# lightmeter_external_batt_circuit.net
KiCad netlist of a schematic drawn in EAGLE
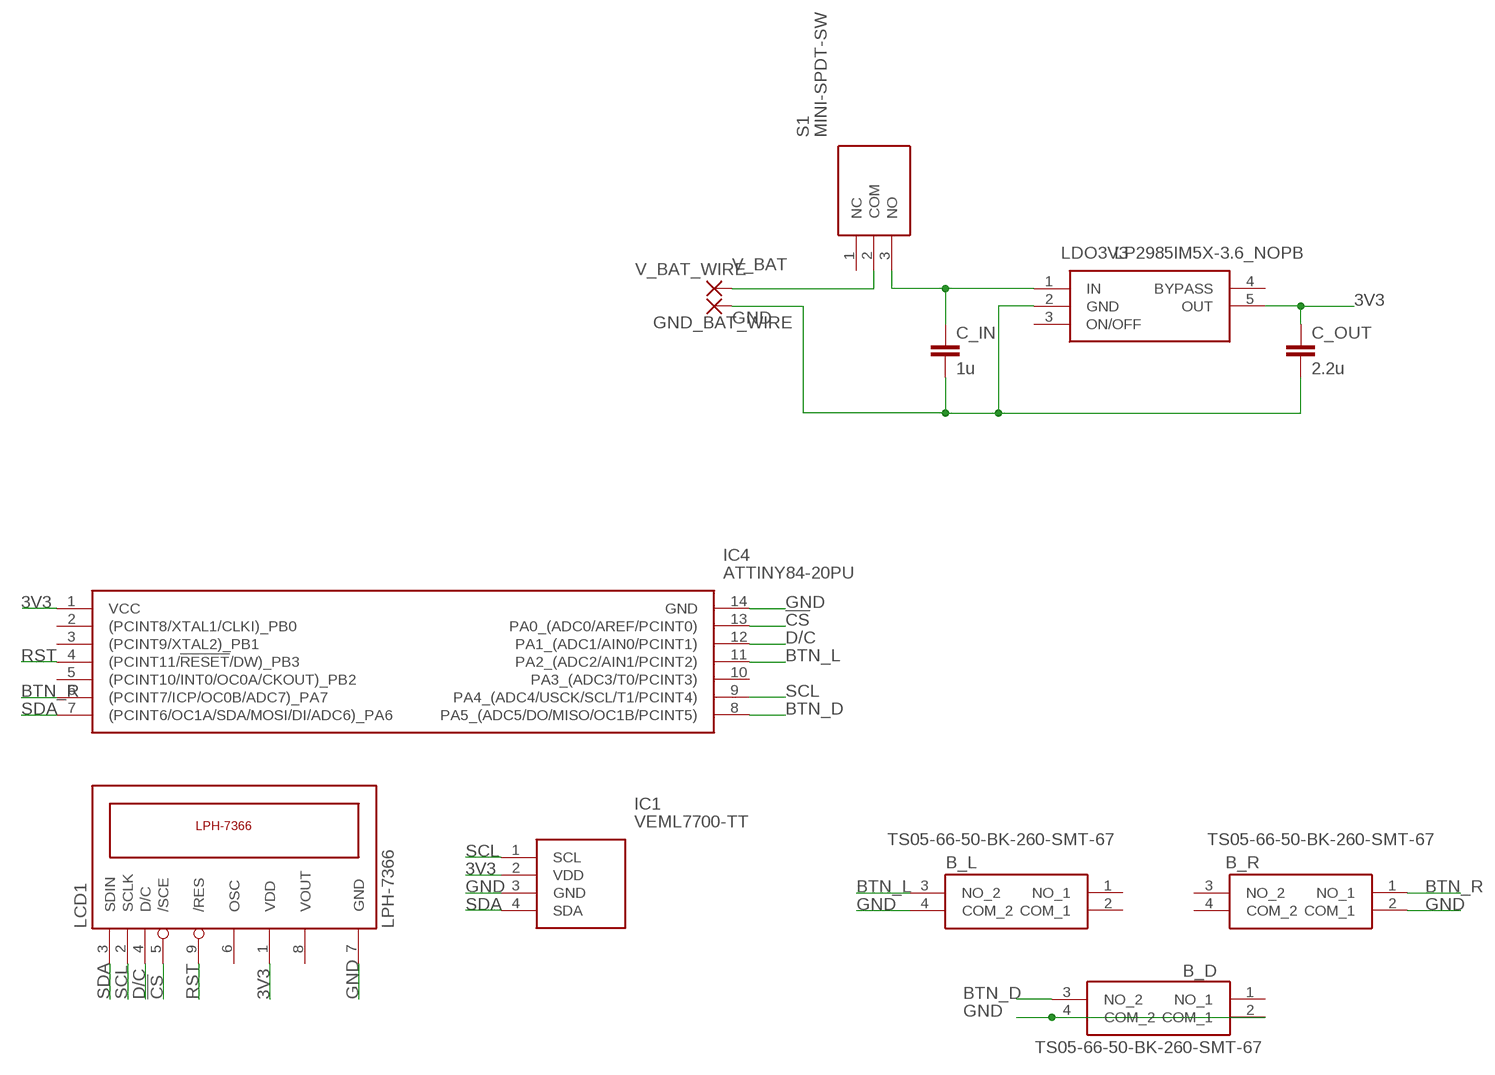
[diagram p0: schematic, sheet 1]

(export (version "E")
  (design (tool "Eeschema 10.0.6"))
  (components
    (comp (ref "B_D")
      (value "TS05-66-50-BK-260-SMT-67")
      (footprint "eagle-import:TS056650BK260SMT67")
      (fields (field (name "MOUSER_PART_NUMBER") "179-TS056650260SMT67"))
      (libsource (lib "eagle-import") (part "TS05-66-50-BK-260-SMT-67"))
    )
    (comp (ref "B_L")
      (value "TS05-66-50-BK-260-SMT-67")
      (footprint "eagle-import:TS056650BK260SMT67")
      (fields (field (name "MOUSER_PART_NUMBER") "179-TS056650260SMT67"))
      (libsource (lib "eagle-import") (part "TS05-66-50-BK-260-SMT-67"))
    )
    (comp (ref "B_R")
      (value "TS05-66-50-BK-260-SMT-67")
      (footprint "eagle-import:TS056650BK260SMT67")
      (fields (field (name "MOUSER_PART_NUMBER") "179-TS056650260SMT67"))
      (libsource (lib "eagle-import") (part "TS05-66-50-BK-260-SMT-67"))
    )
    (comp (ref "C_IN")
      (value "1u")
      (footprint "eagle-import:C3216")
      (libsource (lib "eagle-import") (part "C-EUC3216"))
    )
    (comp (ref "C_OUT")
      (value "2.2u")
      (footprint "eagle-import:C3216")
      (libsource (lib "eagle-import") (part "C-EUC3216"))
    )
    (comp (ref "GND_BAT_WIRE")
      (value "2,54/0,9")
      (footprint "eagle-import:2,54_0,9")
      (libsource (lib "eagle-import") (part "2,54/0,9"))
    )
    (comp (ref "IC1")
      (value "VEML7700-TT")
      (footprint "eagle-import:VEML7700")
      (fields (field (name "MOUSER_PART_NUMBER") "78-VEML7700-TT"))
      (libsource (lib "eagle-import") (part "VEML7700-TT"))
    )
    (comp (ref "IC4")
      (value "ATTINY84-20PU")
      (footprint "eagle-import:DIP794W56P254L1918H533Q14N")
      (fields (field (name "MOUSER_PART_NUMBER") "556-ATTINY84-20PU"))
      (libsource (lib "eagle-import") (part "ATTINY84-20PU"))
    )
    (comp (ref "LCD1")
      (value "LPH-7366")
      (footprint "eagle-import:LPH-7366")
      (libsource (lib "eagle-import") (part "LPH-7366"))
    )
    (comp (ref "LDO3V3")
      (value "LP2985IM5X-3.6_NOPB")
      (footprint "eagle-import:SOT95P280X145-5N")
      (fields
        (field (name "MANUFACTURER_PART_NUMBER") "LP2985IM5X-3.6/NOPB")
        (field (name "MOUSER_PART_NUMBER") "926-LP2985IM5X36NOPB")
      )
      (libsource (lib "eagle-import") (part "LP2985IM5X-3.6_NOPB"))
    )
    (comp (ref "S1")
      (value "MINI-SPDT-SW")
      (footprint "eagle-import:MINISPDTSW")
      (fields (field (name "MOUSER_PART_NUMBER") "992-MINI-SPDT-SW"))
      (libsource (lib "eagle-import") (part "MINI-SPDT-SW"))
    )
    (comp (ref "V_BAT_WIRE")
      (value "2,54/0,9")
      (footprint "eagle-import:2,54_0,9")
      (libsource (lib "eagle-import") (part "2,54/0,9"))
    )
  )
  (nets
    (net (code "1") (name "/3V3") (class "Default")
      (node (ref "C_OUT") (pin "1") (pinfunction "1_1") (pintype "passive"))
      (node (ref "IC1") (pin "2") (pinfunction "VDD_2") (pintype "bidirectional"))
      (node (ref "IC4") (pin "1") (pinfunction "VCC_1") (pintype "bidirectional"))
      (node (ref "LCD1") (pin "1") (pinfunction "VDD_1") (pintype "power_in"))
      (node (ref "LDO3V3") (pin "5") (pinfunction "OUT_5") (pintype "bidirectional"))
    )
    (net (code "2") (name "/BTN_D") (class "Default")
      (node (ref "B_D") (pin "3") (pinfunction "NO_2_3") (pintype "bidirectional"))
      (node (ref "IC4") (pin "8") (pinfunction "PA5_(ADC5/DO/MISO/OC1B/PCINT5)_8") (pintype "bidirectional"))
    )
    (net (code "3") (name "/BTN_L") (class "Default")
      (node (ref "B_L") (pin "3") (pinfunction "NO_2_3") (pintype "bidirectional"))
      (node (ref "IC4") (pin "11") (pinfunction "PA2_(ADC2/AIN1/PCINT2)_11") (pintype "bidirectional"))
    )
    (net (code "4") (name "/BTN_R") (class "Default")
      (node (ref "B_R") (pin "1") (pinfunction "NO_1_1") (pintype "bidirectional"))
      (node (ref "IC4") (pin "6") (pinfunction "(PCINT7/ICP/OC0B/ADC7)_PA7_6") (pintype "bidirectional"))
    )
    (net (code "5") (name "/D{slash}C") (class "Default")
      (node (ref "IC4") (pin "12") (pinfunction "PA1_(ADC1/AIN0/PCINT1)_12") (pintype "bidirectional"))
      (node (ref "LCD1") (pin "4") (pinfunction "D/C_4") (pintype "input"))
    )
    (net (code "6") (name "/GND") (class "Default")
      (node (ref "B_D") (pin "2") (pinfunction "COM_1_2") (pintype "bidirectional"))
      (node (ref "B_D") (pin "4") (pinfunction "COM_2_4") (pintype "bidirectional"))
      (node (ref "B_L") (pin "4") (pinfunction "COM_2_4") (pintype "bidirectional"))
      (node (ref "B_R") (pin "2") (pinfunction "COM_1_2") (pintype "bidirectional"))
      (node (ref "C_IN") (pin "2") (pinfunction "2_2") (pintype "passive"))
      (node (ref "C_OUT") (pin "2") (pinfunction "2_2") (pintype "passive"))
      (node (ref "GND_BAT_WIRE") (pin "1") (pinfunction "P_1") (pintype "passive"))
      (node (ref "IC1") (pin "3") (pinfunction "GND_3") (pintype "bidirectional"))
      (node (ref "IC4") (pin "14") (pinfunction "GND_14") (pintype "bidirectional"))
      (node (ref "LCD1") (pin "7") (pinfunction "GND_7") (pintype "power_in"))
      (node (ref "LDO3V3") (pin "2") (pinfunction "GND_2") (pintype "bidirectional"))
    )
    (net (code "7") (name "/RST") (class "Default")
      (node (ref "IC4") (pin "4") (pinfunction "(PCINT11/~{RESET}/DW)_PB3_4") (pintype "bidirectional"))
      (node (ref "LCD1") (pin "9") (pinfunction "/RES_9") (pintype "input"))
    )
    (net (code "8") (name "/SCL") (class "Default")
      (node (ref "IC1") (pin "1") (pinfunction "SCL_1") (pintype "bidirectional"))
      (node (ref "IC4") (pin "9") (pinfunction "PA4_(ADC4/USCK/SCL/T1/PCINT4)_9") (pintype "bidirectional"))
      (node (ref "LCD1") (pin "2") (pinfunction "SCLK_2") (pintype "input"))
    )
    (net (code "9") (name "/SDA") (class "Default")
      (node (ref "IC1") (pin "4") (pinfunction "SDA_4") (pintype "bidirectional"))
      (node (ref "IC4") (pin "7") (pinfunction "(PCINT6/OC1A/SDA/MOSI/DI/ADC6)_PA6_7") (pintype "bidirectional"))
      (node (ref "LCD1") (pin "3") (pinfunction "SDIN_3") (pintype "input"))
    )
    (net (code "10") (name "/V_BAT") (class "Default")
      (node (ref "S1") (pin "2") (pinfunction "COM_2") (pintype "bidirectional"))
      (node (ref "V_BAT_WIRE") (pin "1") (pinfunction "P_1") (pintype "passive"))
    )
    (net (code "11") (name "/~{CS}") (class "Default")
      (node (ref "IC4") (pin "13") (pinfunction "PA0_(ADC0/AREF/PCINT0)_13") (pintype "bidirectional"))
      (node (ref "LCD1") (pin "5") (pinfunction "/SCE_5") (pintype "input"))
    )
    (net (code "12") (name "Net-(LDO3V3-IN)") (class "Default")
      (node (ref "C_IN") (pin "1") (pinfunction "1_1") (pintype "passive"))
      (node (ref "LDO3V3") (pin "1") (pinfunction "IN_1") (pintype "bidirectional"))
      (node (ref "S1") (pin "3") (pinfunction "NO_3") (pintype "bidirectional"))
    )
    (net (code "13") (name "unconnected-(B_D-NO_1-Pad1)") (class "Default")
      (node (ref "B_D") (pin "1") (pinfunction "NO_1_1") (pintype "bidirectional"))
    )
    (net (code "14") (name "unconnected-(B_L-COM_1-Pad2)") (class "Default")
      (node (ref "B_L") (pin "2") (pinfunction "COM_1_2") (pintype "bidirectional"))
    )
    (net (code "15") (name "unconnected-(B_L-NO_1-Pad1)") (class "Default")
      (node (ref "B_L") (pin "1") (pinfunction "NO_1_1") (pintype "bidirectional"))
    )
    (net (code "16") (name "unconnected-(B_R-COM_2-Pad4)") (class "Default")
      (node (ref "B_R") (pin "4") (pinfunction "COM_2_4") (pintype "bidirectional"))
    )
    (net (code "17") (name "unconnected-(B_R-NO_2-Pad3)") (class "Default")
      (node (ref "B_R") (pin "3") (pinfunction "NO_2_3") (pintype "bidirectional"))
    )
    (net (code "18") (name "unconnected-(IC4-(PCINT8{slash}XTAL1{slash}CLKI)_PB0-Pad2)") (class "Default")
      (node (ref "IC4") (pin "2") (pinfunction "(PCINT8/XTAL1/CLKI)_PB0_2") (pintype "bidirectional"))
    )
    (net (code "19") (name "unconnected-(IC4-(PCINT9{slash}XTAL2)_PB1-Pad3)") (class "Default")
      (node (ref "IC4") (pin "3") (pinfunction "(PCINT9/XTAL2)_PB1_3") (pintype "bidirectional"))
    )
    (net (code "20") (name "unconnected-(IC4-(PCINT10{slash}INT0{slash}OC0A{slash}CKOUT)_PB2-Pad5)") (class "Default")
      (node (ref "IC4") (pin "5") (pinfunction "(PCINT10/INT0/OC0A/CKOUT)_PB2_5") (pintype "bidirectional"))
    )
    (net (code "21") (name "unconnected-(IC4-PA3_(ADC3{slash}T0{slash}PCINT3)-Pad10)") (class "Default")
      (node (ref "IC4") (pin "10") (pinfunction "PA3_(ADC3/T0/PCINT3)_10") (pintype "bidirectional"))
    )
    (net (code "22") (name "unconnected-(LCD1-OSC-Pad6)") (class "Default")
      (node (ref "LCD1") (pin "6") (pinfunction "OSC_6") (pintype "passive"))
    )
    (net (code "23") (name "unconnected-(LCD1-VOUT-Pad8)") (class "Default")
      (node (ref "LCD1") (pin "8") (pinfunction "VOUT_8") (pintype "passive"))
    )
    (net (code "24") (name "unconnected-(LDO3V3-BYPASS-Pad4)") (class "Default")
      (node (ref "LDO3V3") (pin "4") (pinfunction "BYPASS_4") (pintype "bidirectional"))
    )
    (net (code "25") (name "unconnected-(LDO3V3-ON{slash}OFF-Pad3)") (class "Default")
      (node (ref "LDO3V3") (pin "3") (pinfunction "ON/OFF_3") (pintype "bidirectional"))
    )
    (net (code "26") (name "unconnected-(S1-NC-Pad1)") (class "Default")
      (node (ref "S1") (pin "1") (pinfunction "NC_1") (pintype "no_connect"))
    )
  )
)
